# TI_FREQ.net
KiCad netlist of a schematic drawn in Altium Designer
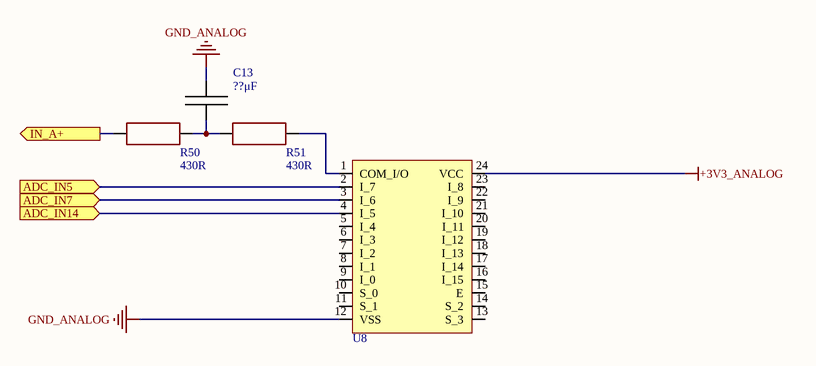
[diagram p0: TI_FREQ.SchDoc]

(export (version "E")
  (design (tool "Eeschema 10.0.6"))
  (components
    (comp (ref "C13")
      (value "??μF")
      (footprint "CAP: 0603")
      (fields (field (name "VOLTAGE") "??V") (field (name "Comment") "Cap_0603"))
      (libsource (lib "capacitor") (part "Cap_0603"))
    )
    (comp (ref "R50")
      (value "430R")
      (footprint "RES: 0603")
      (fields
        (field (name "POWER") "0.1W")
        (field (name "TOLERANCE") "±5%")
        (field (name "Comment") "Resistor_0603")
      )
      (libsource (lib "resistor") (part "Resistor_0603"))
    )
    (comp (ref "R51")
      (value "430R")
      (footprint "RES: 0603")
      (fields
        (field (name "POWER") "0.1W")
        (field (name "TOLERANCE") "±5%")
        (field (name "Comment") "Resistor_0603")
      )
      (libsource (lib "resistor") (part "Resistor_0603"))
    )
    (comp (ref "U8")
      (value "CD74HC4067M96")
      (footprint "SOIC-24")
      (description "1 MHz, Low-Power Op Amp")
      (fields (field (name "MANUFACTURER") "Texas Instruments"))
      (libsource (lib "MY_INT_LIB") (part "CD74HC4067M96"))
    )
  )
  (nets
    (net (code "1") (name "+3V3_ANALOG") (class "Default")
      (node (ref "U8") (pin "24") (pinfunction "VCC_24") (pintype "power_in"))
    )
    (net (code "2") (name "/ADC_IN5") (class "Default")
      (node (ref "U8") (pin "2") (pinfunction "I_7_2") (pintype "passive"))
    )
    (net (code "3") (name "/ADC_IN7") (class "Default")
      (node (ref "U8") (pin "3") (pinfunction "I_6_3") (pintype "passive"))
    )
    (net (code "4") (name "/ADC_IN14") (class "Default")
      (node (ref "U8") (pin "4") (pinfunction "I_5_4") (pintype "passive"))
    )
    (net (code "5") (name "/IN_A+") (class "Default")
      (node (ref "R50") (pin "1") (pinfunction "1_1") (pintype "passive"))
    )
    (net (code "6") (name "GND_ANALOG") (class "Default")
      (node (ref "C13") (pin "2") (pinfunction "2_2") (pintype "passive"))
      (node (ref "U8") (pin "12") (pinfunction "VSS_12") (pintype "power_in"))
    )
    (net (code "7") (name "Net-(C13-Pad1)") (class "Default")
      (node (ref "C13") (pin "1") (pinfunction "1_1") (pintype "passive"))
      (node (ref "R50") (pin "2") (pinfunction "2_2") (pintype "passive"))
      (node (ref "R51") (pin "1") (pinfunction "1_1") (pintype "passive"))
    )
    (net (code "8") (name "Net-(U8-COM_I{slash}O)") (class "Default")
      (node (ref "R51") (pin "2") (pinfunction "2_2") (pintype "passive"))
      (node (ref "U8") (pin "1") (pinfunction "COM_I/O_1") (pintype "passive"))
    )
    (net (code "9") (name "unconnected-(U8-E-Pad15)") (class "Default")
      (node (ref "U8") (pin "15") (pinfunction "E_15") (pintype "passive"))
    )
    (net (code "10") (name "unconnected-(U8-I_0-Pad9)") (class "Default")
      (node (ref "U8") (pin "9") (pinfunction "I_0_9") (pintype "passive"))
    )
    (net (code "11") (name "unconnected-(U8-I_1-Pad8)") (class "Default")
      (node (ref "U8") (pin "8") (pinfunction "I_1_8") (pintype "passive"))
    )
    (net (code "12") (name "unconnected-(U8-I_2-Pad7)") (class "Default")
      (node (ref "U8") (pin "7") (pinfunction "I_2_7") (pintype "passive"))
    )
    (net (code "13") (name "unconnected-(U8-I_3-Pad6)") (class "Default")
      (node (ref "U8") (pin "6") (pinfunction "I_3_6") (pintype "passive"))
    )
    (net (code "14") (name "unconnected-(U8-I_4-Pad5)") (class "Default")
      (node (ref "U8") (pin "5") (pinfunction "I_4_5") (pintype "passive"))
    )
    (net (code "15") (name "unconnected-(U8-I_8-Pad23)") (class "Default")
      (node (ref "U8") (pin "23") (pinfunction "I_8_23") (pintype "passive"))
    )
    (net (code "16") (name "unconnected-(U8-I_9-Pad22)") (class "Default")
      (node (ref "U8") (pin "22") (pinfunction "I_9_22") (pintype "passive"))
    )
    (net (code "17") (name "unconnected-(U8-I_10-Pad21)") (class "Default")
      (node (ref "U8") (pin "21") (pinfunction "I_10_21") (pintype "passive"))
    )
    (net (code "18") (name "unconnected-(U8-I_11-Pad20)") (class "Default")
      (node (ref "U8") (pin "20") (pinfunction "I_11_20") (pintype "passive"))
    )
    (net (code "19") (name "unconnected-(U8-I_12-Pad19)") (class "Default")
      (node (ref "U8") (pin "19") (pinfunction "I_12_19") (pintype "passive"))
    )
    (net (code "20") (name "unconnected-(U8-I_13-Pad18)") (class "Default")
      (node (ref "U8") (pin "18") (pinfunction "I_13_18") (pintype "passive"))
    )
    (net (code "21") (name "unconnected-(U8-I_14-Pad17)") (class "Default")
      (node (ref "U8") (pin "17") (pinfunction "I_14_17") (pintype "passive"))
    )
    (net (code "22") (name "unconnected-(U8-I_15-Pad16)") (class "Default")
      (node (ref "U8") (pin "16") (pinfunction "I_15_16") (pintype "passive"))
    )
    (net (code "23") (name "unconnected-(U8-S_0-Pad10)") (class "Default")
      (node (ref "U8") (pin "10") (pinfunction "S_0_10") (pintype "passive"))
    )
    (net (code "24") (name "unconnected-(U8-S_1-Pad11)") (class "Default")
      (node (ref "U8") (pin "11") (pinfunction "S_1_11") (pintype "passive"))
    )
    (net (code "25") (name "unconnected-(U8-S_2-Pad14)") (class "Default")
      (node (ref "U8") (pin "14") (pinfunction "S_2_14") (pintype "passive"))
    )
    (net (code "26") (name "unconnected-(U8-S_3-Pad13)") (class "Default")
      (node (ref "U8") (pin "13") (pinfunction "S_3_13") (pintype "passive"))
    )
  )
)
